# DoubleSwitch.net
KiCad netlist of a schematic drawn in EAGLE
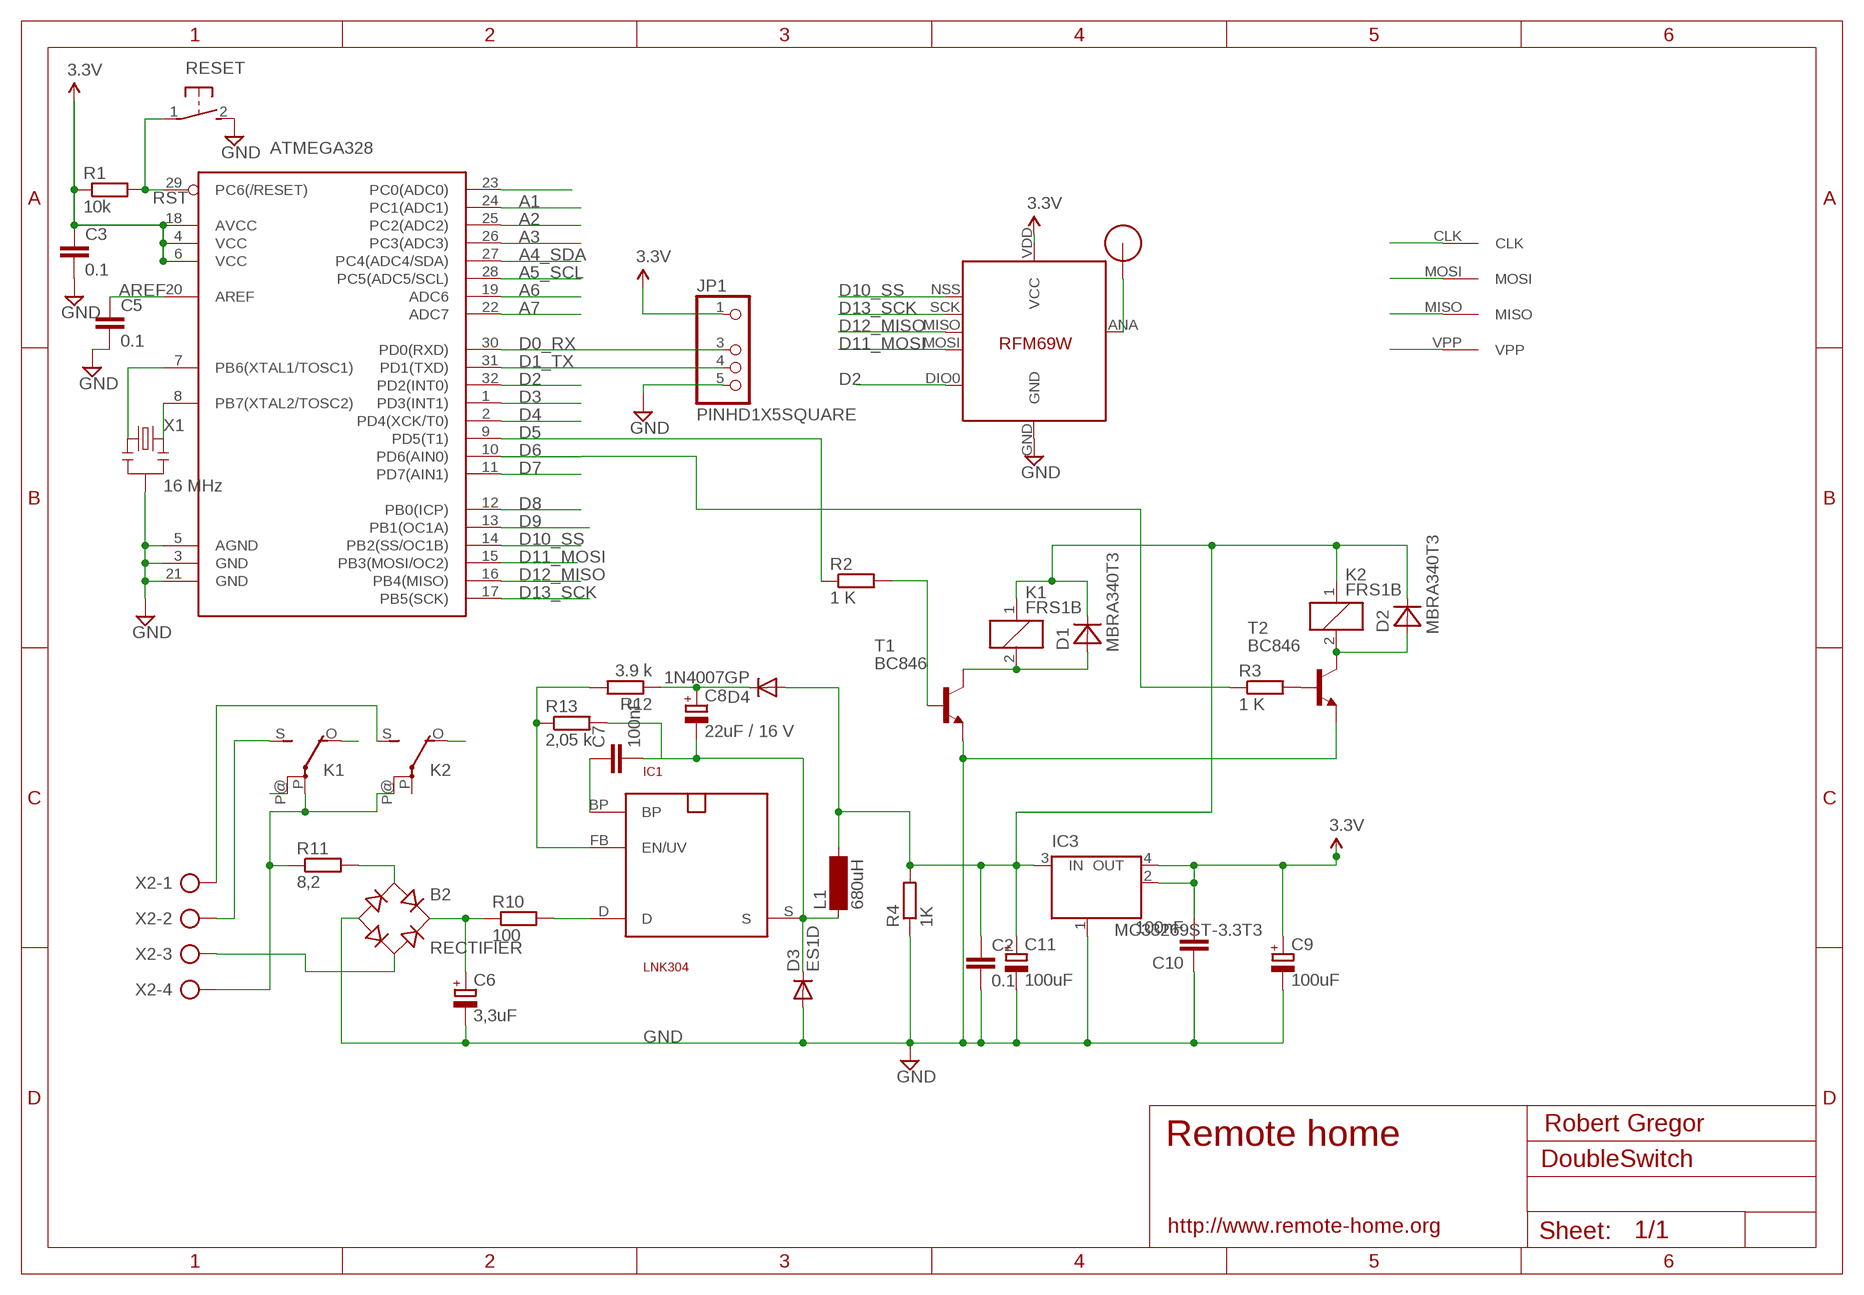
[diagram p0: schematic, sheet 1]

(export (version "E")
  (design (tool "Eeschema 10.0.6"))
  (components
    (comp (ref "ATMEGA328")
      (value "ATMega-328")
      (footprint "eagle-import:TQFP32-08")
      (libsource (lib "eagle-import") (part "ATMEGA168/328TQFP32"))
    )
    (comp (ref "B2")
      (value "RECTIFIER")
      (footprint "eagle-import:TO-269AA")
      (libsource (lib "eagle-import") (part "RECTIFIER-S40"))
    )
    (comp (ref "C2")
      (value "0.1")
      (footprint "eagle-import:C2012")
      (libsource (lib "eagle-import") (part "C-EUC2012"))
    )
    (comp (ref "C3")
      (value "0.1")
      (footprint "eagle-import:C2012")
      (libsource (lib "eagle-import") (part "C-EUC2012"))
    )
    (comp (ref "C5")
      (value "0.1")
      (footprint "eagle-import:C2012")
      (libsource (lib "eagle-import") (part "C-EUC2012"))
    )
    (comp (ref "C6")
      (value "3,3uF")
      (footprint "eagle-import:E5-10,5")
      (libsource (lib "eagle-import") (part "CPOL-EUE5-10.5"))
    )
    (comp (ref "C7")
      (value "100nF")
      (footprint "eagle-import:C2012")
      (libsource (lib "eagle-import") (part "C-EUC2012"))
    )
    (comp (ref "C8")
      (value "22uF / 16 V")
      (footprint "eagle-import:SMC_C")
      (libsource (lib "eagle-import") (part "CPOL-EUSMCC"))
    )
    (comp (ref "C9")
      (value "100uF")
      (footprint "eagle-import:SMC_B")
      (libsource (lib "eagle-import") (part "CPOL-EUSMCB"))
    )
    (comp (ref "C10")
      (value "100nF")
      (footprint "eagle-import:C2012")
      (libsource (lib "eagle-import") (part "C-EUC2012"))
    )
    (comp (ref "C11")
      (value "100uF")
      (footprint "eagle-import:SMC_B")
      (libsource (lib "eagle-import") (part "CPOL-EUSMCB"))
    )
    (comp (ref "D1")
      (value "MBRA340T3")
      (footprint "eagle-import:SMA")
      (libsource (lib "eagle-import") (part "MBRA340T3"))
    )
    (comp (ref "D2")
      (value "MBRA340T3")
      (footprint "eagle-import:SMA")
      (libsource (lib "eagle-import") (part "MBRA340T3"))
    )
    (comp (ref "D3")
      (value "ES1D")
      (footprint "eagle-import:DO214AC")
      (libsource (lib "eagle-import") (part "DIODE-DO214AC"))
    )
    (comp (ref "D4")
      (value "1N4007GP")
      (footprint "eagle-import:DO214AA")
      (libsource (lib "eagle-import") (part "DIODE-DO214AA"))
    )
    (comp (ref "IC1")
      (value "LNK304")
      (footprint "eagle-import:SO-8C")
      (libsource (lib "eagle-import") (part "SO-8C"))
    )
    (comp (ref "IC3")
      (value "MC33269ST-3.3T3")
      (footprint "eagle-import:SOT223")
      (libsource (lib "eagle-import") (part "MC33269ST-3.3T3"))
    )
    (comp (ref "JP1")
      (value "PINHD1X5SQUARE")
      (footprint "eagle-import:PINHD1X05-SQUARE")
      (libsource (lib "eagle-import") (part "PINHD1X5SQUARE"))
    )
    (comp (ref "K1")
      (value "FRS1B")
      (footprint "eagle-import:FRS1B")
      (libsource (lib "eagle-import") (part "FRS1B"))
    )
    (comp (ref "K2")
      (value "FRS1B")
      (footprint "eagle-import:FRS1B")
      (libsource (lib "eagle-import") (part "FRS1B"))
    )
    (comp (ref "L1")
      (value "680uH")
      (footprint "eagle-import:BS11")
      (libsource (lib "eagle-import") (part "BS11"))
    )
    (comp (ref "R1")
      (value "10k")
      (footprint "eagle-import:M2012")
      (libsource (lib "eagle-import") (part "R-EU_M2012"))
    )
    (comp (ref "R2")
      (value "1 K")
      (footprint "eagle-import:M2012")
      (libsource (lib "eagle-import") (part "R-EU_M2012"))
    )
    (comp (ref "R3")
      (value "1 K")
      (footprint "eagle-import:M2012")
      (libsource (lib "eagle-import") (part "R-EU_M2012"))
    )
    (comp (ref "R4")
      (value "1K")
      (footprint "eagle-import:M2012")
      (libsource (lib "eagle-import") (part "R-EU_M2012"))
    )
    (comp (ref "R10")
      (value "100")
      (footprint "eagle-import:R2512W")
      (libsource (lib "eagle-import") (part "R-EU_R2512W"))
    )
    (comp (ref "R11")
      (value "8,2")
      (footprint "eagle-import:0411_12")
      (libsource (lib "eagle-import") (part "R-EU_0411/12"))
    )
    (comp (ref "R12")
      (value "3.9 k")
      (footprint "eagle-import:M2012")
      (libsource (lib "eagle-import") (part "R-EU_M2012"))
    )
    (comp (ref "R13")
      (value "2,05 k")
      (footprint "eagle-import:M2012")
      (libsource (lib "eagle-import") (part "R-EU_M2012"))
    )
    (comp (ref "RESET")
      (value "DTSM-3")
      (footprint "eagle-import:DTSM-3")
      (libsource (lib "eagle-import") (part "DTSM-3"))
    )
    (comp (ref "T1")
      (value "BC846")
      (footprint "eagle-import:SOT23")
      (libsource (lib "eagle-import") (part "BC846"))
    )
    (comp (ref "T2")
      (value "BC846")
      (footprint "eagle-import:SOT23")
      (libsource (lib "eagle-import") (part "BC846"))
    )
    (comp (ref "U$1")
      (value "RFM12B_ANTENNA")
      (footprint "eagle-import:RFM12B-ANTENNA")
      (libsource (lib "eagle-import") (part "RFM12B_ANTENNA"))
    )
    (comp (ref "U$2")
      (value "AVRHEADERDIP")
      (footprint "eagle-import:AVRHEADER")
      (libsource (lib "eagle-import") (part "AVRHEADERDIP"))
    )
    (comp (ref "U$5")
      (value "RFM69")
      (footprint "eagle-import:RFM69W-MINPADS")
      (libsource (lib "eagle-import") (part "RFM69"))
    )
    (comp (ref "X1")
      (value "16 MHz")
      (footprint "eagle-import:RESONATOR-SMD")
      (libsource (lib "eagle-import") (part "RESONATORSMD"))
    )
    (comp (ref "X2")
      (value "AK500/4")
      (footprint "eagle-import:AK500_4")
      (libsource (lib "eagle-import") (part "AK500/4"))
    )
  )
  (nets
    (net (code "1") (name "/A1") (class "Default")
      (node (ref "ATMEGA328") (pin "24") (pinfunction "PC1(ADC1)_24") (pintype "bidirectional"))
    )
    (net (code "2") (name "/A2") (class "Default")
      (node (ref "ATMEGA328") (pin "25") (pinfunction "PC2(ADC2)_25") (pintype "bidirectional"))
    )
    (net (code "3") (name "/A3") (class "Default")
      (node (ref "ATMEGA328") (pin "26") (pinfunction "PC3(ADC3)_26") (pintype "bidirectional"))
    )
    (net (code "4") (name "/A4_SDA") (class "Default")
      (node (ref "ATMEGA328") (pin "27") (pinfunction "PC4(ADC4/SDA)_27") (pintype "bidirectional"))
    )
    (net (code "5") (name "/A5_SCL") (class "Default")
      (node (ref "ATMEGA328") (pin "28") (pinfunction "PC5(ADC5/SCL)_28") (pintype "bidirectional"))
    )
    (net (code "6") (name "/A6") (class "Default")
      (node (ref "ATMEGA328") (pin "19") (pinfunction "ADC6_19") (pintype "bidirectional"))
    )
    (net (code "7") (name "/A7") (class "Default")
      (node (ref "ATMEGA328") (pin "22") (pinfunction "ADC7_22") (pintype "bidirectional"))
    )
    (net (code "8") (name "/AREF") (class "Default")
      (node (ref "ATMEGA328") (pin "20") (pinfunction "AREF_20") (pintype "bidirectional"))
      (node (ref "C5") (pin "1") (pinfunction "1_1") (pintype "passive"))
    )
    (net (code "9") (name "/D0_RX") (class "Default")
      (node (ref "ATMEGA328") (pin "30") (pinfunction "PD0(RXD)_30") (pintype "bidirectional"))
      (node (ref "JP1") (pin "3") (pinfunction "3_3") (pintype "passive"))
    )
    (net (code "10") (name "/D1_TX") (class "Default")
      (node (ref "ATMEGA328") (pin "31") (pinfunction "PD1(TXD)_31") (pintype "bidirectional"))
      (node (ref "JP1") (pin "4") (pinfunction "4_4") (pintype "passive"))
    )
    (net (code "11") (name "/D2") (class "Default")
      (node (ref "ATMEGA328") (pin "32") (pinfunction "PD2(INT0)_32") (pintype "bidirectional"))
      (node (ref "U$5") (pin "DIO0") (pinfunction "DIO0_DIO0") (pintype "open_collector"))
    )
    (net (code "12") (name "/D3") (class "Default")
      (node (ref "ATMEGA328") (pin "1") (pinfunction "PD3(INT1)_1") (pintype "bidirectional"))
    )
    (net (code "13") (name "/D4") (class "Default")
      (node (ref "ATMEGA328") (pin "2") (pinfunction "PD4(XCK/T0)_2") (pintype "bidirectional"))
    )
    (net (code "14") (name "/D5") (class "Default")
      (node (ref "ATMEGA328") (pin "9") (pinfunction "PD5(T1)_9") (pintype "bidirectional"))
      (node (ref "R2") (pin "1") (pinfunction "1_1") (pintype "passive"))
    )
    (net (code "15") (name "/D6") (class "Default")
      (node (ref "ATMEGA328") (pin "10") (pinfunction "PD6(AIN0)_10") (pintype "bidirectional"))
      (node (ref "R3") (pin "1") (pinfunction "1_1") (pintype "passive"))
    )
    (net (code "16") (name "/D7") (class "Default")
      (node (ref "ATMEGA328") (pin "11") (pinfunction "PD7(AIN1)_11") (pintype "bidirectional"))
    )
    (net (code "17") (name "/D8") (class "Default")
      (node (ref "ATMEGA328") (pin "12") (pinfunction "PB0(ICP)_12") (pintype "bidirectional"))
    )
    (net (code "18") (name "/D9") (class "Default")
      (node (ref "ATMEGA328") (pin "13") (pinfunction "PB1(OC1A)_13") (pintype "bidirectional"))
    )
    (net (code "19") (name "/D10_SS") (class "Default")
      (node (ref "ATMEGA328") (pin "14") (pinfunction "PB2(SS/OC1B)_14") (pintype "bidirectional"))
      (node (ref "U$5") (pin "NSS") (pinfunction "SEL_NSS") (pintype "input"))
    )
    (net (code "20") (name "/D11_MOSI") (class "Default")
      (node (ref "ATMEGA328") (pin "15") (pinfunction "PB3(MOSI/OC2)_15") (pintype "bidirectional"))
      (node (ref "U$2") (pin "MOSI") (pinfunction "MOSI_MOSI") (pintype "bidirectional"))
      (node (ref "U$5") (pin "MOSI") (pinfunction "MOSI_MOSI") (pintype "output"))
    )
    (net (code "21") (name "/D12_MISO") (class "Default")
      (node (ref "ATMEGA328") (pin "16") (pinfunction "PB4(MISO)_16") (pintype "bidirectional"))
      (node (ref "U$2") (pin "MISO") (pinfunction "MISO_MISO") (pintype "bidirectional"))
      (node (ref "U$5") (pin "MISO") (pinfunction "MISO_MISO") (pintype "input"))
    )
    (net (code "22") (name "/D13_SCK") (class "Default")
      (node (ref "ATMEGA328") (pin "17") (pinfunction "PB5(SCK)_17") (pintype "bidirectional"))
      (node (ref "U$2") (pin "CLK") (pinfunction "CLK_CLK") (pintype "bidirectional"))
      (node (ref "U$5") (pin "SCK") (pinfunction "SCK_SCK") (pintype "input"))
    )
    (net (code "23") (name "/RST") (class "Default")
      (node (ref "ATMEGA328") (pin "29") (pinfunction "PC6(/RESET)_29") (pintype "bidirectional"))
      (node (ref "R1") (pin "2") (pinfunction "2_2") (pintype "passive"))
      (node (ref "RESET") (pin "1") (pinfunction "1_1") (pintype "passive"))
      (node (ref "U$2") (pin "VPP") (pinfunction "VPP_VPP") (pintype "bidirectional"))
    )
    (net (code "24") (name "3.3V") (class "Default")
      (node (ref "ATMEGA328") (pin "18") (pinfunction "AVCC_18") (pintype "bidirectional"))
      (node (ref "ATMEGA328") (pin "4") (pinfunction "VCC_4") (pintype "bidirectional"))
      (node (ref "ATMEGA328") (pin "6") (pinfunction "VCC_6") (pintype "bidirectional"))
      (node (ref "C10") (pin "2") (pinfunction "2_2") (pintype "passive"))
      (node (ref "C3") (pin "1") (pinfunction "1_1") (pintype "passive"))
      (node (ref "C9") (pin "+") (pinfunction "+_+") (pintype "passive"))
      (node (ref "IC3") (pin "2") (pinfunction "OUT_2") (pintype "passive"))
      (node (ref "IC3") (pin "4") (pinfunction "OUT_4") (pintype "passive"))
      (node (ref "JP1") (pin "1") (pinfunction "1_1") (pintype "passive"))
      (node (ref "R1") (pin "1") (pinfunction "1_1") (pintype "passive"))
      (node (ref "U$5") (pin "VDD") (pinfunction "VCC_VDD") (pintype "power_in"))
    )
    (net (code "25") (name "GND") (class "Default")
      (node (ref "ATMEGA328") (pin "21") (pinfunction "GND_21") (pintype "bidirectional"))
      (node (ref "ATMEGA328") (pin "3") (pinfunction "GND_3") (pintype "bidirectional"))
      (node (ref "ATMEGA328") (pin "5") (pinfunction "AGND_5") (pintype "bidirectional"))
      (node (ref "B2") (pin "-") (pinfunction "-_-") (pintype "passive"))
      (node (ref "C10") (pin "1") (pinfunction "1_1") (pintype "passive"))
      (node (ref "C11") (pin "-") (pinfunction "-_-") (pintype "passive"))
      (node (ref "C2") (pin "2") (pinfunction "2_2") (pintype "passive"))
      (node (ref "C3") (pin "2") (pinfunction "2_2") (pintype "passive"))
      (node (ref "C5") (pin "2") (pinfunction "2_2") (pintype "passive"))
      (node (ref "C6") (pin "-") (pinfunction "-_-") (pintype "passive"))
      (node (ref "C9") (pin "-") (pinfunction "-_-") (pintype "passive"))
      (node (ref "D3") (pin "A") (pinfunction "A_A") (pintype "passive"))
      (node (ref "IC3") (pin "1") (pinfunction "GND/ADJ_1") (pintype "input"))
      (node (ref "JP1") (pin "5") (pinfunction "5_5") (pintype "passive"))
      (node (ref "R4") (pin "1") (pinfunction "1_1") (pintype "passive"))
      (node (ref "RESET") (pin "2") (pinfunction "2_2") (pintype "passive"))
      (node (ref "T1") (pin "2") (pinfunction "E_2") (pintype "passive"))
      (node (ref "T2") (pin "2") (pinfunction "E_2") (pintype "passive"))
      (node (ref "U$5") (pin "GND") (pinfunction "GND_GND") (pintype "power_in"))
      (node (ref "X1") (pin "2") (pinfunction "2_2") (pintype "passive"))
    )
    (net (code "26") (name "Net-(ATMEGA328-PB6(XTAL1{slash}TOSC1))") (class "Default")
      (node (ref "ATMEGA328") (pin "7") (pinfunction "PB6(XTAL1/TOSC1)_7") (pintype "bidirectional"))
      (node (ref "X1") (pin "1") (pinfunction "1_1") (pintype "passive"))
    )
    (net (code "27") (name "Net-(ATMEGA328-PB7(XTAL2{slash}TOSC2))") (class "Default")
      (node (ref "ATMEGA328") (pin "8") (pinfunction "PB7(XTAL2/TOSC2)_8") (pintype "bidirectional"))
      (node (ref "X1") (pin "3") (pinfunction "3_3") (pintype "passive"))
    )
    (net (code "28") (name "Net-(B2-Pad+)") (class "Default")
      (node (ref "B2") (pin "+") (pinfunction "+_+") (pintype "passive"))
      (node (ref "C6") (pin "+") (pinfunction "+_+") (pintype "passive"))
      (node (ref "R10") (pin "1") (pinfunction "1_1") (pintype "passive"))
    )
    (net (code "29") (name "Net-(B2-PadAC1)") (class "Default")
      (node (ref "B2") (pin "AC1") (pinfunction "AC1_AC1") (pintype "passive"))
      (node (ref "R11") (pin "2") (pinfunction "2_2") (pintype "passive"))
    )
    (net (code "30") (name "Net-(C7-Pad1)") (class "Default")
      (node (ref "C7") (pin "1") (pinfunction "1_1") (pintype "passive"))
      (node (ref "IC1") (pin "BP") (pinfunction "BP_BP") (pintype "passive"))
    )
    (net (code "31") (name "Net-(C7-Pad2)") (class "Default")
      (node (ref "C7") (pin "2") (pinfunction "2_2") (pintype "passive"))
      (node (ref "C8") (pin "-") (pinfunction "-_-") (pintype "passive"))
      (node (ref "D3") (pin "C") (pinfunction "C_C") (pintype "passive"))
      (node (ref "IC1") (pin "S") (pinfunction "S_S") (pintype "power_in"))
      (node (ref "L1") (pin "1") (pinfunction "1_1") (pintype "passive"))
      (node (ref "R13") (pin "2") (pinfunction "2_2") (pintype "passive"))
    )
    (net (code "32") (name "Net-(C8-Pad+)") (class "Default")
      (node (ref "C8") (pin "+") (pinfunction "+_+") (pintype "passive"))
      (node (ref "D4") (pin "C") (pinfunction "C_C") (pintype "passive"))
      (node (ref "R12") (pin "1") (pinfunction "1_1") (pintype "passive"))
    )
    (net (code "33") (name "Net-(IC1-EN{slash}UV)") (class "Default")
      (node (ref "IC1") (pin "FB") (pinfunction "EN/UV_FB") (pintype "input"))
      (node (ref "R12") (pin "2") (pinfunction "2_2") (pintype "passive"))
      (node (ref "R13") (pin "1") (pinfunction "1_1") (pintype "passive"))
    )
    (net (code "34") (name "Net-(IC1-PadD)") (class "Default")
      (node (ref "IC1") (pin "D") (pinfunction "D_D") (pintype "open_collector"))
      (node (ref "R10") (pin "2") (pinfunction "2_2") (pintype "passive"))
    )
    (net (code "35") (name "Net-(IC3-IN)") (class "Default")
      (node (ref "C11") (pin "+") (pinfunction "+_+") (pintype "passive"))
      (node (ref "C2") (pin "1") (pinfunction "1_1") (pintype "passive"))
      (node (ref "D1") (pin "C") (pinfunction "C_C") (pintype "passive"))
      (node (ref "D2") (pin "C") (pinfunction "C_C") (pintype "passive"))
      (node (ref "D4") (pin "A") (pinfunction "A_A") (pintype "passive"))
      (node (ref "IC3") (pin "3") (pinfunction "IN_3") (pintype "input"))
      (node (ref "K1") (pin "1") (pinfunction "1_1") (pintype "passive"))
      (node (ref "K2") (pin "1") (pinfunction "1_1") (pintype "passive"))
      (node (ref "L1") (pin "2") (pinfunction "2_2") (pintype "passive"))
      (node (ref "R4") (pin "2") (pinfunction "2_2") (pintype "passive"))
    )
    (net (code "36") (name "Net-(T1-B)") (class "Default")
      (node (ref "R2") (pin "2") (pinfunction "2_2") (pintype "passive"))
      (node (ref "T1") (pin "1") (pinfunction "B_1") (pintype "passive"))
    )
    (net (code "37") (name "Net-(T1-C)") (class "Default")
      (node (ref "D1") (pin "A") (pinfunction "A_A") (pintype "passive"))
      (node (ref "K1") (pin "2") (pinfunction "2_2") (pintype "passive"))
      (node (ref "T1") (pin "3") (pinfunction "C_3") (pintype "passive"))
    )
    (net (code "38") (name "Net-(T2-B)") (class "Default")
      (node (ref "R3") (pin "2") (pinfunction "2_2") (pintype "passive"))
      (node (ref "T2") (pin "1") (pinfunction "B_1") (pintype "passive"))
    )
    (net (code "39") (name "Net-(T2-C)") (class "Default")
      (node (ref "D2") (pin "A") (pinfunction "A_A") (pintype "passive"))
      (node (ref "K2") (pin "2") (pinfunction "2_2") (pintype "passive"))
      (node (ref "T2") (pin "3") (pinfunction "C_3") (pintype "passive"))
    )
    (net (code "40") (name "Net-(U$1-1)") (class "Default")
      (node (ref "U$1") (pin "P$1") (pinfunction "1_P$1") (pintype "bidirectional"))
      (node (ref "U$5") (pin "ANA") (pinfunction "ANT_ANA") (pintype "passive"))
    )
    (net (code "41") (name "Net-(X2A-KL)") (class "Default")
      (node (ref "K2") (pin "S") (pinfunction "S_S") (pintype "passive"))
      (node (ref "X2") (pin "1") (pinfunction "KL_1") (pintype "passive"))
    )
    (net (code "42") (name "Net-(X2B-KL)") (class "Default")
      (node (ref "K1") (pin "S") (pinfunction "S_S") (pintype "passive"))
      (node (ref "X2") (pin "2") (pinfunction "KL_2") (pintype "passive"))
    )
    (net (code "43") (name "Net-(X2C-KL)") (class "Default")
      (node (ref "B2") (pin "AC2") (pinfunction "AC2_AC2") (pintype "passive"))
      (node (ref "X2") (pin "3") (pinfunction "KL_3") (pintype "passive"))
    )
    (net (code "44") (name "Net-(X2D-KL)") (class "Default")
      (node (ref "K1") (pin "P") (pinfunction "P_P") (pintype "passive"))
      (node (ref "K2") (pin "P@") (pinfunction "P_P@") (pintype "passive"))
      (node (ref "R11") (pin "1") (pinfunction "1_1") (pintype "passive"))
      (node (ref "X2") (pin "4") (pinfunction "KL_4") (pintype "passive"))
    )
    (net (code "45") (name "unconnected-(ATMEGA328-PC0(ADC0)-Pad23)") (class "Default")
      (node (ref "ATMEGA328") (pin "23") (pinfunction "PC0(ADC0)_23") (pintype "bidirectional"))
    )
    (net (code "46") (name "unconnected-(K1-PadO)") (class "Default")
      (node (ref "K1") (pin "O") (pinfunction "O_O") (pintype "passive"))
    )
    (net (code "47") (name "unconnected-(K1B-P-PadP@)") (class "Default")
      (node (ref "K1") (pin "P@") (pinfunction "P_P@") (pintype "passive"))
    )
    (net (code "48") (name "unconnected-(K2-PadO)") (class "Default")
      (node (ref "K2") (pin "O") (pinfunction "O_O") (pintype "passive"))
    )
    (net (code "49") (name "unconnected-(K2-PadP)") (class "Default")
      (node (ref "K2") (pin "P") (pinfunction "P_P") (pintype "passive"))
    )
  )
)
